# GS_02_Pow.net
KiCad netlist of a schematic drawn in Altium Designer
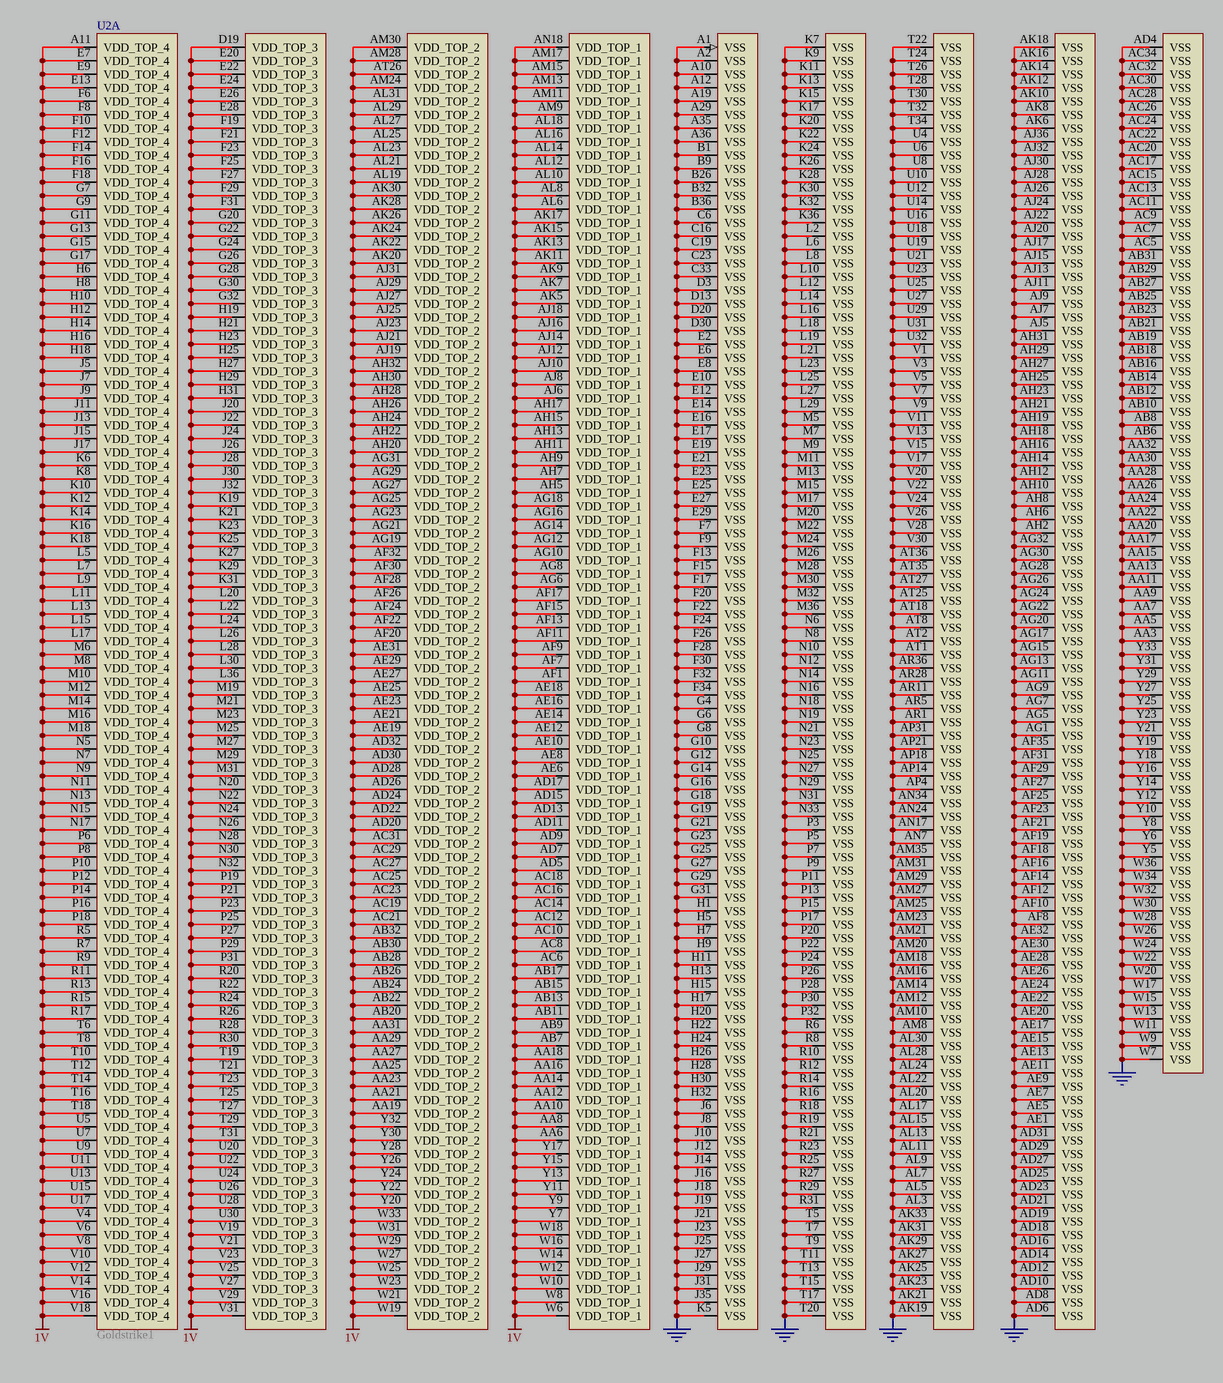
[diagram p0: GS_02_Pow.SchDoc]

(export (version "E")
  (design (tool "Eeschema 10.0.6"))
  (components (comp (ref "U2") (value "Goldstrike1") (libsource (lib "Schlib1") (part "Goldstrike1"))))
  (nets
    (net (code "1") (name "1V") (class "Default")
      (node (ref "U2") (pin "A11") (pinfunction "VDD_TOP_4_A11") (pintype "passive"))
      (node (ref "U2") (pin "AA10") (pinfunction "VDD_TOP_1_AA10") (pintype "passive"))
      (node (ref "U2") (pin "AA12") (pinfunction "VDD_TOP_1_AA12") (pintype "passive"))
      (node (ref "U2") (pin "AA14") (pinfunction "VDD_TOP_1_AA14") (pintype "passive"))
      (node (ref "U2") (pin "AA16") (pinfunction "VDD_TOP_1_AA16") (pintype "passive"))
      (node (ref "U2") (pin "AA18") (pinfunction "VDD_TOP_1_AA18") (pintype "passive"))
      (node (ref "U2") (pin "AA19") (pinfunction "VDD_TOP_2_AA19") (pintype "passive"))
      (node (ref "U2") (pin "AA21") (pinfunction "VDD_TOP_2_AA21") (pintype "passive"))
      (node (ref "U2") (pin "AA23") (pinfunction "VDD_TOP_2_AA23") (pintype "passive"))
      (node (ref "U2") (pin "AA25") (pinfunction "VDD_TOP_2_AA25") (pintype "passive"))
      (node (ref "U2") (pin "AA27") (pinfunction "VDD_TOP_2_AA27") (pintype "passive"))
      (node (ref "U2") (pin "AA29") (pinfunction "VDD_TOP_2_AA29") (pintype "passive"))
      (node (ref "U2") (pin "AA31") (pinfunction "VDD_TOP_2_AA31") (pintype "passive"))
      (node (ref "U2") (pin "AA6") (pinfunction "VDD_TOP_1_AA6") (pintype "passive"))
      (node (ref "U2") (pin "AA8") (pinfunction "VDD_TOP_1_AA8") (pintype "passive"))
      (node (ref "U2") (pin "AB11") (pinfunction "VDD_TOP_1_AB11") (pintype "passive"))
      (node (ref "U2") (pin "AB13") (pinfunction "VDD_TOP_1_AB13") (pintype "passive"))
      (node (ref "U2") (pin "AB15") (pinfunction "VDD_TOP_1_AB15") (pintype "passive"))
      (node (ref "U2") (pin "AB17") (pinfunction "VDD_TOP_1_AB17") (pintype "passive"))
      (node (ref "U2") (pin "AB20") (pinfunction "VDD_TOP_2_AB20") (pintype "passive"))
      (node (ref "U2") (pin "AB22") (pinfunction "VDD_TOP_2_AB22") (pintype "passive"))
      (node (ref "U2") (pin "AB24") (pinfunction "VDD_TOP_2_AB24") (pintype "passive"))
      (node (ref "U2") (pin "AB26") (pinfunction "VDD_TOP_2_AB26") (pintype "passive"))
      (node (ref "U2") (pin "AB28") (pinfunction "VDD_TOP_2_AB28") (pintype "passive"))
      (node (ref "U2") (pin "AB30") (pinfunction "VDD_TOP_2_AB30") (pintype "passive"))
      (node (ref "U2") (pin "AB32") (pinfunction "VDD_TOP_2_AB32") (pintype "passive"))
      (node (ref "U2") (pin "AB7") (pinfunction "VDD_TOP_1_AB7") (pintype "passive"))
      (node (ref "U2") (pin "AB9") (pinfunction "VDD_TOP_1_AB9") (pintype "passive"))
      (node (ref "U2") (pin "AC10") (pinfunction "VDD_TOP_1_AC10") (pintype "passive"))
      (node (ref "U2") (pin "AC12") (pinfunction "VDD_TOP_1_AC12") (pintype "passive"))
      (node (ref "U2") (pin "AC14") (pinfunction "VDD_TOP_1_AC14") (pintype "passive"))
      (node (ref "U2") (pin "AC16") (pinfunction "VDD_TOP_1_AC16") (pintype "passive"))
      (node (ref "U2") (pin "AC18") (pinfunction "VDD_TOP_1_AC18") (pintype "passive"))
      (node (ref "U2") (pin "AC19") (pinfunction "VDD_TOP_2_AC19") (pintype "passive"))
      (node (ref "U2") (pin "AC21") (pinfunction "VDD_TOP_2_AC21") (pintype "passive"))
      (node (ref "U2") (pin "AC23") (pinfunction "VDD_TOP_2_AC23") (pintype "passive"))
      (node (ref "U2") (pin "AC25") (pinfunction "VDD_TOP_2_AC25") (pintype "passive"))
      (node (ref "U2") (pin "AC27") (pinfunction "VDD_TOP_2_AC27") (pintype "passive"))
      (node (ref "U2") (pin "AC29") (pinfunction "VDD_TOP_2_AC29") (pintype "passive"))
      (node (ref "U2") (pin "AC31") (pinfunction "VDD_TOP_2_AC31") (pintype "passive"))
      (node (ref "U2") (pin "AC6") (pinfunction "VDD_TOP_1_AC6") (pintype "passive"))
      (node (ref "U2") (pin "AC8") (pinfunction "VDD_TOP_1_AC8") (pintype "passive"))
      (node (ref "U2") (pin "AD11") (pinfunction "VDD_TOP_1_AD11") (pintype "passive"))
      (node (ref "U2") (pin "AD13") (pinfunction "VDD_TOP_1_AD13") (pintype "passive"))
      (node (ref "U2") (pin "AD15") (pinfunction "VDD_TOP_1_AD15") (pintype "passive"))
      (node (ref "U2") (pin "AD17") (pinfunction "VDD_TOP_1_AD17") (pintype "passive"))
      (node (ref "U2") (pin "AD20") (pinfunction "VDD_TOP_2_AD20") (pintype "passive"))
      (node (ref "U2") (pin "AD22") (pinfunction "VDD_TOP_2_AD22") (pintype "passive"))
      (node (ref "U2") (pin "AD24") (pinfunction "VDD_TOP_2_AD24") (pintype "passive"))
      (node (ref "U2") (pin "AD26") (pinfunction "VDD_TOP_2_AD26") (pintype "passive"))
      (node (ref "U2") (pin "AD28") (pinfunction "VDD_TOP_2_AD28") (pintype "passive"))
      (node (ref "U2") (pin "AD30") (pinfunction "VDD_TOP_2_AD30") (pintype "passive"))
      (node (ref "U2") (pin "AD32") (pinfunction "VDD_TOP_2_AD32") (pintype "passive"))
      (node (ref "U2") (pin "AD5") (pinfunction "VDD_TOP_1_AD5") (pintype "passive"))
      (node (ref "U2") (pin "AD7") (pinfunction "VDD_TOP_1_AD7") (pintype "passive"))
      (node (ref "U2") (pin "AD9") (pinfunction "VDD_TOP_1_AD9") (pintype "passive"))
      (node (ref "U2") (pin "AE10") (pinfunction "VDD_TOP_1_AE10") (pintype "passive"))
      (node (ref "U2") (pin "AE12") (pinfunction "VDD_TOP_1_AE12") (pintype "passive"))
      (node (ref "U2") (pin "AE14") (pinfunction "VDD_TOP_1_AE14") (pintype "passive"))
      (node (ref "U2") (pin "AE16") (pinfunction "VDD_TOP_1_AE16") (pintype "passive"))
      (node (ref "U2") (pin "AE18") (pinfunction "VDD_TOP_1_AE18") (pintype "passive"))
      (node (ref "U2") (pin "AE19") (pinfunction "VDD_TOP_2_AE19") (pintype "passive"))
      (node (ref "U2") (pin "AE21") (pinfunction "VDD_TOP_2_AE21") (pintype "passive"))
      (node (ref "U2") (pin "AE23") (pinfunction "VDD_TOP_2_AE23") (pintype "passive"))
      (node (ref "U2") (pin "AE25") (pinfunction "VDD_TOP_2_AE25") (pintype "passive"))
      (node (ref "U2") (pin "AE27") (pinfunction "VDD_TOP_2_AE27") (pintype "passive"))
      (node (ref "U2") (pin "AE29") (pinfunction "VDD_TOP_2_AE29") (pintype "passive"))
      (node (ref "U2") (pin "AE31") (pinfunction "VDD_TOP_2_AE31") (pintype "passive"))
      (node (ref "U2") (pin "AE6") (pinfunction "VDD_TOP_1_AE6") (pintype "passive"))
      (node (ref "U2") (pin "AE8") (pinfunction "VDD_TOP_1_AE8") (pintype "passive"))
      (node (ref "U2") (pin "AF1") (pinfunction "VDD_TOP_1_AF1") (pintype "passive"))
      (node (ref "U2") (pin "AF11") (pinfunction "VDD_TOP_1_AF11") (pintype "passive"))
      (node (ref "U2") (pin "AF13") (pinfunction "VDD_TOP_1_AF13") (pintype "passive"))
      (node (ref "U2") (pin "AF15") (pinfunction "VDD_TOP_1_AF15") (pintype "passive"))
      (node (ref "U2") (pin "AF17") (pinfunction "VDD_TOP_1_AF17") (pintype "passive"))
      (node (ref "U2") (pin "AF20") (pinfunction "VDD_TOP_2_AF20") (pintype "passive"))
      (node (ref "U2") (pin "AF22") (pinfunction "VDD_TOP_2_AF22") (pintype "passive"))
      (node (ref "U2") (pin "AF24") (pinfunction "VDD_TOP_2_AF24") (pintype "passive"))
      (node (ref "U2") (pin "AF26") (pinfunction "VDD_TOP_2_AF26") (pintype "passive"))
      (node (ref "U2") (pin "AF28") (pinfunction "VDD_TOP_2_AF28") (pintype "passive"))
      (node (ref "U2") (pin "AF30") (pinfunction "VDD_TOP_2_AF30") (pintype "passive"))
      (node (ref "U2") (pin "AF32") (pinfunction "VDD_TOP_2_AF32") (pintype "passive"))
      (node (ref "U2") (pin "AF7") (pinfunction "VDD_TOP_1_AF7") (pintype "passive"))
      (node (ref "U2") (pin "AF9") (pinfunction "VDD_TOP_1_AF9") (pintype "passive"))
      (node (ref "U2") (pin "AG10") (pinfunction "VDD_TOP_1_AG10") (pintype "passive"))
      (node (ref "U2") (pin "AG12") (pinfunction "VDD_TOP_1_AG12") (pintype "passive"))
      (node (ref "U2") (pin "AG14") (pinfunction "VDD_TOP_1_AG14") (pintype "passive"))
      (node (ref "U2") (pin "AG16") (pinfunction "VDD_TOP_1_AG16") (pintype "passive"))
      (node (ref "U2") (pin "AG18") (pinfunction "VDD_TOP_1_AG18") (pintype "passive"))
      (node (ref "U2") (pin "AG19") (pinfunction "VDD_TOP_2_AG19") (pintype "passive"))
      (node (ref "U2") (pin "AG21") (pinfunction "VDD_TOP_2_AG21") (pintype "passive"))
      (node (ref "U2") (pin "AG23") (pinfunction "VDD_TOP_2_AG23") (pintype "passive"))
      (node (ref "U2") (pin "AG25") (pinfunction "VDD_TOP_2_AG25") (pintype "passive"))
      (node (ref "U2") (pin "AG27") (pinfunction "VDD_TOP_2_AG27") (pintype "passive"))
      (node (ref "U2") (pin "AG29") (pinfunction "VDD_TOP_2_AG29") (pintype "passive"))
      (node (ref "U2") (pin "AG31") (pinfunction "VDD_TOP_2_AG31") (pintype "passive"))
      (node (ref "U2") (pin "AG6") (pinfunction "VDD_TOP_1_AG6") (pintype "passive"))
      (node (ref "U2") (pin "AG8") (pinfunction "VDD_TOP_1_AG8") (pintype "passive"))
      (node (ref "U2") (pin "AH11") (pinfunction "VDD_TOP_1_AH11") (pintype "passive"))
      (node (ref "U2") (pin "AH13") (pinfunction "VDD_TOP_1_AH13") (pintype "passive"))
      (node (ref "U2") (pin "AH15") (pinfunction "VDD_TOP_1_AH15") (pintype "passive"))
      (node (ref "U2") (pin "AH17") (pinfunction "VDD_TOP_1_AH17") (pintype "passive"))
      (node (ref "U2") (pin "AH20") (pinfunction "VDD_TOP_2_AH20") (pintype "passive"))
      (node (ref "U2") (pin "AH22") (pinfunction "VDD_TOP_2_AH22") (pintype "passive"))
      (node (ref "U2") (pin "AH24") (pinfunction "VDD_TOP_2_AH24") (pintype "passive"))
      (node (ref "U2") (pin "AH26") (pinfunction "VDD_TOP_2_AH26") (pintype "passive"))
      (node (ref "U2") (pin "AH28") (pinfunction "VDD_TOP_2_AH28") (pintype "passive"))
      (node (ref "U2") (pin "AH30") (pinfunction "VDD_TOP_2_AH30") (pintype "passive"))
      (node (ref "U2") (pin "AH32") (pinfunction "VDD_TOP_2_AH32") (pintype "passive"))
      (node (ref "U2") (pin "AH5") (pinfunction "VDD_TOP_1_AH5") (pintype "passive"))
      (node (ref "U2") (pin "AH7") (pinfunction "VDD_TOP_1_AH7") (pintype "passive"))
      (node (ref "U2") (pin "AH9") (pinfunction "VDD_TOP_1_AH9") (pintype "passive"))
      (node (ref "U2") (pin "AJ10") (pinfunction "VDD_TOP_1_AJ10") (pintype "passive"))
      (node (ref "U2") (pin "AJ12") (pinfunction "VDD_TOP_1_AJ12") (pintype "passive"))
      (node (ref "U2") (pin "AJ14") (pinfunction "VDD_TOP_1_AJ14") (pintype "passive"))
      (node (ref "U2") (pin "AJ16") (pinfunction "VDD_TOP_1_AJ16") (pintype "passive"))
      (node (ref "U2") (pin "AJ18") (pinfunction "VDD_TOP_1_AJ18") (pintype "passive"))
      (node (ref "U2") (pin "AJ19") (pinfunction "VDD_TOP_2_AJ19") (pintype "passive"))
      (node (ref "U2") (pin "AJ21") (pinfunction "VDD_TOP_2_AJ21") (pintype "passive"))
      (node (ref "U2") (pin "AJ23") (pinfunction "VDD_TOP_2_AJ23") (pintype "passive"))
      (node (ref "U2") (pin "AJ25") (pinfunction "VDD_TOP_2_AJ25") (pintype "passive"))
      (node (ref "U2") (pin "AJ27") (pinfunction "VDD_TOP_2_AJ27") (pintype "passive"))
      (node (ref "U2") (pin "AJ29") (pinfunction "VDD_TOP_2_AJ29") (pintype "passive"))
      (node (ref "U2") (pin "AJ31") (pinfunction "VDD_TOP_2_AJ31") (pintype "passive"))
      (node (ref "U2") (pin "AJ6") (pinfunction "VDD_TOP_1_AJ6") (pintype "passive"))
      (node (ref "U2") (pin "AJ8") (pinfunction "VDD_TOP_1_AJ8") (pintype "passive"))
      (node (ref "U2") (pin "AK11") (pinfunction "VDD_TOP_1_AK11") (pintype "passive"))
      (node (ref "U2") (pin "AK13") (pinfunction "VDD_TOP_1_AK13") (pintype "passive"))
      (node (ref "U2") (pin "AK15") (pinfunction "VDD_TOP_1_AK15") (pintype "passive"))
      (node (ref "U2") (pin "AK17") (pinfunction "VDD_TOP_1_AK17") (pintype "passive"))
      (node (ref "U2") (pin "AK20") (pinfunction "VDD_TOP_2_AK20") (pintype "passive"))
      (node (ref "U2") (pin "AK22") (pinfunction "VDD_TOP_2_AK22") (pintype "passive"))
      (node (ref "U2") (pin "AK24") (pinfunction "VDD_TOP_2_AK24") (pintype "passive"))
      (node (ref "U2") (pin "AK26") (pinfunction "VDD_TOP_2_AK26") (pintype "passive"))
      (node (ref "U2") (pin "AK28") (pinfunction "VDD_TOP_2_AK28") (pintype "passive"))
      (node (ref "U2") (pin "AK30") (pinfunction "VDD_TOP_2_AK30") (pintype "passive"))
      (node (ref "U2") (pin "AK5") (pinfunction "VDD_TOP_1_AK5") (pintype "passive"))
      (node (ref "U2") (pin "AK7") (pinfunction "VDD_TOP_1_AK7") (pintype "passive"))
      (node (ref "U2") (pin "AK9") (pinfunction "VDD_TOP_1_AK9") (pintype "passive"))
      (node (ref "U2") (pin "AL10") (pinfunction "VDD_TOP_1_AL10") (pintype "passive"))
      (node (ref "U2") (pin "AL12") (pinfunction "VDD_TOP_1_AL12") (pintype "passive"))
      (node (ref "U2") (pin "AL14") (pinfunction "VDD_TOP_1_AL14") (pintype "passive"))
      (node (ref "U2") (pin "AL16") (pinfunction "VDD_TOP_1_AL16") (pintype "passive"))
      (node (ref "U2") (pin "AL18") (pinfunction "VDD_TOP_1_AL18") (pintype "passive"))
      (node (ref "U2") (pin "AL19") (pinfunction "VDD_TOP_2_AL19") (pintype "passive"))
      (node (ref "U2") (pin "AL21") (pinfunction "VDD_TOP_2_AL21") (pintype "passive"))
      (node (ref "U2") (pin "AL23") (pinfunction "VDD_TOP_2_AL23") (pintype "passive"))
      (node (ref "U2") (pin "AL25") (pinfunction "VDD_TOP_2_AL25") (pintype "passive"))
      (node (ref "U2") (pin "AL27") (pinfunction "VDD_TOP_2_AL27") (pintype "passive"))
      (node (ref "U2") (pin "AL29") (pinfunction "VDD_TOP_2_AL29") (pintype "passive"))
      (node (ref "U2") (pin "AL31") (pinfunction "VDD_TOP_2_AL31") (pintype "passive"))
      (node (ref "U2") (pin "AL6") (pinfunction "VDD_TOP_1_AL6") (pintype "passive"))
      (node (ref "U2") (pin "AL8") (pinfunction "VDD_TOP_1_AL8") (pintype "passive"))
      (node (ref "U2") (pin "AM11") (pinfunction "VDD_TOP_1_AM11") (pintype "passive"))
      (node (ref "U2") (pin "AM13") (pinfunction "VDD_TOP_1_AM13") (pintype "passive"))
      (node (ref "U2") (pin "AM15") (pinfunction "VDD_TOP_1_AM15") (pintype "passive"))
      (node (ref "U2") (pin "AM17") (pinfunction "VDD_TOP_1_AM17") (pintype "passive"))
      (node (ref "U2") (pin "AM24") (pinfunction "VDD_TOP_2_AM24") (pintype "passive"))
      (node (ref "U2") (pin "AM28") (pinfunction "VDD_TOP_2_AM28") (pintype "passive"))
      (node (ref "U2") (pin "AM30") (pinfunction "VDD_TOP_2_AM30") (pintype "passive"))
      (node (ref "U2") (pin "AM9") (pinfunction "VDD_TOP_1_AM9") (pintype "passive"))
      (node (ref "U2") (pin "AN18") (pinfunction "VDD_TOP_1_AN18") (pintype "passive"))
      (node (ref "U2") (pin "AT26") (pinfunction "VDD_TOP_2_AT26") (pintype "passive"))
      (node (ref "U2") (pin "D19") (pinfunction "VDD_TOP_3_D19") (pintype "passive"))
      (node (ref "U2") (pin "E13") (pinfunction "VDD_TOP_4_E13") (pintype "passive"))
      (node (ref "U2") (pin "E20") (pinfunction "VDD_TOP_3_E20") (pintype "passive"))
      (node (ref "U2") (pin "E22") (pinfunction "VDD_TOP_3_E22") (pintype "passive"))
      (node (ref "U2") (pin "E24") (pinfunction "VDD_TOP_3_E24") (pintype "passive"))
      (node (ref "U2") (pin "E26") (pinfunction "VDD_TOP_3_E26") (pintype "passive"))
      (node (ref "U2") (pin "E28") (pinfunction "VDD_TOP_3_E28") (pintype "passive"))
      (node (ref "U2") (pin "E7") (pinfunction "VDD_TOP_4_E7") (pintype "passive"))
      (node (ref "U2") (pin "E9") (pinfunction "VDD_TOP_4_E9") (pintype "passive"))
      (node (ref "U2") (pin "F10") (pinfunction "VDD_TOP_4_F10") (pintype "passive"))
      (node (ref "U2") (pin "F12") (pinfunction "VDD_TOP_4_F12") (pintype "passive"))
      (node (ref "U2") (pin "F14") (pinfunction "VDD_TOP_4_F14") (pintype "passive"))
      (node (ref "U2") (pin "F16") (pinfunction "VDD_TOP_4_F16") (pintype "passive"))
      (node (ref "U2") (pin "F18") (pinfunction "VDD_TOP_4_F18") (pintype "passive"))
      (node (ref "U2") (pin "F19") (pinfunction "VDD_TOP_3_F19") (pintype "passive"))
      (node (ref "U2") (pin "F21") (pinfunction "VDD_TOP_3_F21") (pintype "passive"))
      (node (ref "U2") (pin "F23") (pinfunction "VDD_TOP_3_F23") (pintype "passive"))
      (node (ref "U2") (pin "F25") (pinfunction "VDD_TOP_3_F25") (pintype "passive"))
      (node (ref "U2") (pin "F27") (pinfunction "VDD_TOP_3_F27") (pintype "passive"))
      (node (ref "U2") (pin "F29") (pinfunction "VDD_TOP_3_F29") (pintype "passive"))
      (node (ref "U2") (pin "F31") (pinfunction "VDD_TOP_3_F31") (pintype "passive"))
      (node (ref "U2") (pin "F6") (pinfunction "VDD_TOP_4_F6") (pintype "passive"))
      (node (ref "U2") (pin "F8") (pinfunction "VDD_TOP_4_F8") (pintype "passive"))
      (node (ref "U2") (pin "G11") (pinfunction "VDD_TOP_4_G11") (pintype "passive"))
      (node (ref "U2") (pin "G13") (pinfunction "VDD_TOP_4_G13") (pintype "passive"))
      (node (ref "U2") (pin "G15") (pinfunction "VDD_TOP_4_G15") (pintype "passive"))
      (node (ref "U2") (pin "G17") (pinfunction "VDD_TOP_4_G17") (pintype "passive"))
      (node (ref "U2") (pin "G20") (pinfunction "VDD_TOP_3_G20") (pintype "passive"))
      (node (ref "U2") (pin "G22") (pinfunction "VDD_TOP_3_G22") (pintype "passive"))
      (node (ref "U2") (pin "G24") (pinfunction "VDD_TOP_3_G24") (pintype "passive"))
      (node (ref "U2") (pin "G26") (pinfunction "VDD_TOP_3_G26") (pintype "passive"))
      (node (ref "U2") (pin "G28") (pinfunction "VDD_TOP_3_G28") (pintype "passive"))
      (node (ref "U2") (pin "G30") (pinfunction "VDD_TOP_3_G30") (pintype "passive"))
      (node (ref "U2") (pin "G32") (pinfunction "VDD_TOP_3_G32") (pintype "passive"))
      (node (ref "U2") (pin "G7") (pinfunction "VDD_TOP_4_G7") (pintype "passive"))
      (node (ref "U2") (pin "G9") (pinfunction "VDD_TOP_4_G9") (pintype "passive"))
      (node (ref "U2") (pin "H10") (pinfunction "VDD_TOP_4_H10") (pintype "passive"))
      (node (ref "U2") (pin "H12") (pinfunction "VDD_TOP_4_H12") (pintype "passive"))
      (node (ref "U2") (pin "H14") (pinfunction "VDD_TOP_4_H14") (pintype "passive"))
      (node (ref "U2") (pin "H16") (pinfunction "VDD_TOP_4_H16") (pintype "passive"))
      (node (ref "U2") (pin "H18") (pinfunction "VDD_TOP_4_H18") (pintype "passive"))
      (node (ref "U2") (pin "H19") (pinfunction "VDD_TOP_3_H19") (pintype "passive"))
      (node (ref "U2") (pin "H21") (pinfunction "VDD_TOP_3_H21") (pintype "passive"))
      (node (ref "U2") (pin "H23") (pinfunction "VDD_TOP_3_H23") (pintype "passive"))
      (node (ref "U2") (pin "H25") (pinfunction "VDD_TOP_3_H25") (pintype "passive"))
      (node (ref "U2") (pin "H27") (pinfunction "VDD_TOP_3_H27") (pintype "passive"))
      (node (ref "U2") (pin "H29") (pinfunction "VDD_TOP_3_H29") (pintype "passive"))
      (node (ref "U2") (pin "H31") (pinfunction "VDD_TOP_3_H31") (pintype "passive"))
      (node (ref "U2") (pin "H6") (pinfunction "VDD_TOP_4_H6") (pintype "passive"))
      (node (ref "U2") (pin "H8") (pinfunction "VDD_TOP_4_H8") (pintype "passive"))
      (node (ref "U2") (pin "J11") (pinfunction "VDD_TOP_4_J11") (pintype "passive"))
      (node (ref "U2") (pin "J13") (pinfunction "VDD_TOP_4_J13") (pintype "passive"))
      (node (ref "U2") (pin "J15") (pinfunction "VDD_TOP_4_J15") (pintype "passive"))
      (node (ref "U2") (pin "J17") (pinfunction "VDD_TOP_4_J17") (pintype "passive"))
      (node (ref "U2") (pin "J20") (pinfunction "VDD_TOP_3_J20") (pintype "passive"))
      (node (ref "U2") (pin "J22") (pinfunction "VDD_TOP_3_J22") (pintype "passive"))
      (node (ref "U2") (pin "J24") (pinfunction "VDD_TOP_3_J24") (pintype "passive"))
      (node (ref "U2") (pin "J26") (pinfunction "VDD_TOP_3_J26") (pintype "passive"))
      (node (ref "U2") (pin "J28") (pinfunction "VDD_TOP_3_J28") (pintype "passive"))
      (node (ref "U2") (pin "J30") (pinfunction "VDD_TOP_3_J30") (pintype "passive"))
      (node (ref "U2") (pin "J32") (pinfunction "VDD_TOP_3_J32") (pintype "passive"))
      (node (ref "U2") (pin "J5") (pinfunction "VDD_TOP_4_J5") (pintype "passive"))
      (node (ref "U2") (pin "J7") (pinfunction "VDD_TOP_4_J7") (pintype "passive"))
      (node (ref "U2") (pin "J9") (pinfunction "VDD_TOP_4_J9") (pintype "passive"))
      (node (ref "U2") (pin "K10") (pinfunction "VDD_TOP_4_K10") (pintype "passive"))
      (node (ref "U2") (pin "K12") (pinfunction "VDD_TOP_4_K12") (pintype "passive"))
      (node (ref "U2") (pin "K14") (pinfunction "VDD_TOP_4_K14") (pintype "passive"))
      (node (ref "U2") (pin "K16") (pinfunction "VDD_TOP_4_K16") (pintype "passive"))
      (node (ref "U2") (pin "K18") (pinfunction "VDD_TOP_4_K18") (pintype "passive"))
      (node (ref "U2") (pin "K19") (pinfunction "VDD_TOP_3_K19") (pintype "passive"))
      (node (ref "U2") (pin "K21") (pinfunction "VDD_TOP_3_K21") (pintype "passive"))
      (node (ref "U2") (pin "K23") (pinfunction "VDD_TOP_3_K23") (pintype "passive"))
      (node (ref "U2") (pin "K25") (pinfunction "VDD_TOP_3_K25") (pintype "passive"))
      (node (ref "U2") (pin "K27") (pinfunction "VDD_TOP_3_K27") (pintype "passive"))
      (node (ref "U2") (pin "K29") (pinfunction "VDD_TOP_3_K29") (pintype "passive"))
      (node (ref "U2") (pin "K31") (pinfunction "VDD_TOP_3_K31") (pintype "passive"))
      (node (ref "U2") (pin "K6") (pinfunction "VDD_TOP_4_K6") (pintype "passive"))
      (node (ref "U2") (pin "K8") (pinfunction "VDD_TOP_4_K8") (pintype "passive"))
      (node (ref "U2") (pin "L11") (pinfunction "VDD_TOP_4_L11") (pintype "passive"))
      (node (ref "U2") (pin "L13") (pinfunction "VDD_TOP_4_L13") (pintype "passive"))
      (node (ref "U2") (pin "L15") (pinfunction "VDD_TOP_4_L15") (pintype "passive"))
      (node (ref "U2") (pin "L17") (pinfunction "VDD_TOP_4_L17") (pintype "passive"))
      (node (ref "U2") (pin "L20") (pinfunction "VDD_TOP_3_L20") (pintype "passive"))
      (node (ref "U2") (pin "L22") (pinfunction "VDD_TOP_3_L22") (pintype "passive"))
      (node (ref "U2") (pin "L24") (pinfunction "VDD_TOP_3_L24") (pintype "passive"))
      (node (ref "U2") (pin "L26") (pinfunction "VDD_TOP_3_L26") (pintype "passive"))
      (node (ref "U2") (pin "L28") (pinfunction "VDD_TOP_3_L28") (pintype "passive"))
      (node (ref "U2") (pin "L30") (pinfunction "VDD_TOP_3_L30") (pintype "passive"))
      (node (ref "U2") (pin "L36") (pinfunction "VDD_TOP_3_L36") (pintype "passive"))
      (node (ref "U2") (pin "L5") (pinfunction "VDD_TOP_4_L5") (pintype "passive"))
      (node (ref "U2") (pin "L7") (pinfunction "VDD_TOP_4_L7") (pintype "passive"))
      (node (ref "U2") (pin "L9") (pinfunction "VDD_TOP_4_L9") (pintype "passive"))
      (node (ref "U2") (pin "M10") (pinfunction "VDD_TOP_4_M10") (pintype "passive"))
      (node (ref "U2") (pin "M12") (pinfunction "VDD_TOP_4_M12") (pintype "passive"))
      (node (ref "U2") (pin "M14") (pinfunction "VDD_TOP_4_M14") (pintype "passive"))
      (node (ref "U2") (pin "M16") (pinfunction "VDD_TOP_4_M16") (pintype "passive"))
      (node (ref "U2") (pin "M18") (pinfunction "VDD_TOP_4_M18") (pintype "passive"))
      (node (ref "U2") (pin "M19") (pinfunction "VDD_TOP_3_M19") (pintype "passive"))
      (node (ref "U2") (pin "M21") (pinfunction "VDD_TOP_3_M21") (pintype "passive"))
      (node (ref "U2") (pin "M23") (pinfunction "VDD_TOP_3_M23") (pintype "passive"))
      (node (ref "U2") (pin "M25") (pinfunction "VDD_TOP_3_M25") (pintype "passive"))
      (node (ref "U2") (pin "M27") (pinfunction "VDD_TOP_3_M27") (pintype "passive"))
      (node (ref "U2") (pin "M29") (pinfunction "VDD_TOP_3_M29") (pintype "passive"))
      (node (ref "U2") (pin "M31") (pinfunction "VDD_TOP_3_M31") (pintype "passive"))
      (node (ref "U2") (pin "M6") (pinfunction "VDD_TOP_4_M6") (pintype "passive"))
      (node (ref "U2") (pin "M8") (pinfunction "VDD_TOP_4_M8") (pintype "passive"))
      (node (ref "U2") (pin "N11") (pinfunction "VDD_TOP_4_N11") (pintype "passive"))
      (node (ref "U2") (pin "N13") (pinfunction "VDD_TOP_4_N13") (pintype "passive"))
      (node (ref "U2") (pin "N15") (pinfunction "VDD_TOP_4_N15") (pintype "passive"))
      (node (ref "U2") (pin "N17") (pinfunction "VDD_TOP_4_N17") (pintype "passive"))
      (node (ref "U2") (pin "N20") (pinfunction "VDD_TOP_3_N20") (pintype "passive"))
      (node (ref "U2") (pin "N22") (pinfunction "VDD_TOP_3_N22") (pintype "passive"))
      (node (ref "U2") (pin "N24") (pinfunction "VDD_TOP_3_N24") (pintype "passive"))
      (node (ref "U2") (pin "N26") (pinfunction "VDD_TOP_3_N26") (pintype "passive"))
      (node (ref "U2") (pin "N28") (pinfunction "VDD_TOP_3_N28") (pintype "passive"))
      (node (ref "U2") (pin "N30") (pinfunction "VDD_TOP_3_N30") (pintype "passive"))
      (node (ref "U2") (pin "N32") (pinfunction "VDD_TOP_3_N32") (pintype "passive"))
      (node (ref "U2") (pin "N5") (pinfunction "VDD_TOP_4_N5") (pintype "passive"))
      (node (ref "U2") (pin "N7") (pinfunction "VDD_TOP_4_N7") (pintype "passive"))
      (node (ref "U2") (pin "N9") (pinfunction "VDD_TOP_4_N9") (pintype "passive"))
      (node (ref "U2") (pin "P10") (pinfunction "VDD_TOP_4_P10") (pintype "passive"))
      (node (ref "U2") (pin "P12") (pinfunction "VDD_TOP_4_P12") (pintype "passive"))
      (node (ref "U2") (pin "P14") (pinfunction "VDD_TOP_4_P14") (pintype "passive"))
      (node (ref "U2") (pin "P16") (pinfunction "VDD_TOP_4_P16") (pintype "passive"))
      (node (ref "U2") (pin "P18") (pinfunction "VDD_TOP_4_P18") (pintype "passive"))
      (node (ref "U2") (pin "P19") (pinfunction "VDD_TOP_3_P19") (pintype "passive"))
      (node (ref "U2") (pin "P21") (pinfunction "VDD_TOP_3_P21") (pintype "passive"))
      (node (ref "U2") (pin "P23") (pinfunction "VDD_TOP_3_P23") (pintype "passive"))
      (node (ref "U2") (pin "P25") (pinfunction "VDD_TOP_3_P25") (pintype "passive"))
      (node (ref "U2") (pin "P27") (pinfunction "VDD_TOP_3_P27") (pintype "passive"))
      (node (ref "U2") (pin "P29") (pinfunction "VDD_TOP_3_P29") (pintype "passive"))
      (node (ref "U2") (pin "P31") (pinfunction "VDD_TOP_3_P31") (pintype "passive"))
      (node (ref "U2") (pin "P6") (pinfunction "VDD_TOP_4_P6") (pintype "passive"))
      (node (ref "U2") (pin "P8") (pinfunction "VDD_TOP_4_P8") (pintype "passive"))
      (node (ref "U2") (pin "R11") (pinfunction "VDD_TOP_4_R11") (pintype "passive"))
      (node (ref "U2") (pin "R13") (pinfunction "VDD_TOP_4_R13") (pintype "passive"))
      (node (ref "U2") (pin "R15") (pinfunction "VDD_TOP_4_R15") (pintype "passive"))
      (node (ref "U2") (pin "R17") (pinfunction "VDD_TOP_4_R17") (pintype "passive"))
      (node (ref "U2") (pin "R20") (pinfunction "VDD_TOP_3_R20") (pintype "passive"))
      (node (ref "U2") (pin "R22") (pinfunction "VDD_TOP_3_R22") (pintype "passive"))
      (node (ref "U2") (pin "R24") (pinfunction "VDD_TOP_3_R24") (pintype "passive"))
      (node (ref "U2") (pin "R26") (pinfunction "VDD_TOP_3_R26") (pintype "passive"))
      (node (ref "U2") (pin "R28") (pinfunction "VDD_TOP_3_R28") (pintype "passive"))
      (node (ref "U2") (pin "R30") (pinfunction "VDD_TOP_3_R30") (pintype "passive"))
      (node (ref "U2") (pin "R5") (pinfunction "VDD_TOP_4_R5") (pintype "passive"))
      (node (ref "U2") (pin "R7") (pinfunction "VDD_TOP_4_R7") (pintype "passive"))
      (node (ref "U2") (pin "R9") (pinfunction "VDD_TOP_4_R9") (pintype "passive"))
      (node (ref "U2") (pin "T10") (pinfunction "VDD_TOP_4_T10") (pintype "passive"))
      (node (ref "U2") (pin "T12") (pinfunction "VDD_TOP_4_T12") (pintype "passive"))
      (node (ref "U2") (pin "T14") (pinfunction "VDD_TOP_4_T14") (pintype "passive"))
      (node (ref "U2") (pin "T16") (pinfunction "VDD_TOP_4_T16") (pintype "passive"))
      (node (ref "U2") (pin "T18") (pinfunction "VDD_TOP_4_T18") (pintype "passive"))
      (node (ref "U2") (pin "T19") (pinfunction "VDD_TOP_3_T19") (pintype "passive"))
      (node (ref "U2") (pin "T21") (pinfunction "VDD_TOP_3_T21") (pintype "passive"))
      (node (ref "U2") (pin "T23") (pinfunction "VDD_TOP_3_T23") (pintype "passive"))
      (node (ref "U2") (pin "T25") (pinfunction "VDD_TOP_3_T25") (pintype "passive"))
      (node (ref "U2") (pin "T27") (pinfunction "VDD_TOP_3_T27") (pintype "passive"))
      (node (ref "U2") (pin "T29") (pinfunction "VDD_TOP_3_T29") (pintype "passive"))
      (node (ref "U2") (pin "T31") (pinfunction "VDD_TOP_3_T31") (pintype "passive"))
      (node (ref "U2") (pin "T6") (pinfunction "VDD_TOP_4_T6") (pintype "passive"))
      (node (ref "U2") (pin "T8") (pinfunction "VDD_TOP_4_T8") (pintype "passive"))
      (node (ref "U2") (pin "U11") (pinfunction "VDD_TOP_4_U11") (pintype "passive"))
      (node (ref "U2") (pin "U13") (pinfunction "VDD_TOP_4_U13") (pintype "passive"))
      (node (ref "U2") (pin "U15") (pinfunction "VDD_TOP_4_U15") (pintype "passive"))
      (node (ref "U2") (pin "U17") (pinfunction "VDD_TOP_4_U17") (pintype "passive"))
      (node (ref "U2") (pin "U20") (pinfunction "VDD_TOP_3_U20") (pintype "passive"))
      (node (ref "U2") (pin "U22") (pinfunction "VDD_TOP_3_U22") (pintype "passive"))
      (node (ref "U2") (pin "U24") (pinfunction "VDD_TOP_3_U24") (pintype "passive"))
      (node (ref "U2") (pin "U26") (pinfunction "VDD_TOP_3_U26") (pintype "passive"))
      (node (ref "U2") (pin "U28") (pinfunction "VDD_TOP_3_U28") (pintype "passive"))
      (node (ref "U2") (pin "U30") (pinfunction "VDD_TOP_3_U30") (pintype "passive"))
      (node (ref "U2") (pin "U5") (pinfunction "VDD_TOP_4_U5") (pintype "passive"))
      (node (ref "U2") (pin "U7") (pinfunction "VDD_TOP_4_U7") (pintype "passive"))
      (node (ref "U2") (pin "U9") (pinfunction "VDD_TOP_4_U9") (pintype "passive"))
      (node (ref "U2") (pin "V10") (pinfunction "VDD_TOP_4_V10") (pintype "passive"))
      (node (ref "U2") (pin "V12") (pinfunction "VDD_TOP_4_V12") (pintype "passive"))
      (node (ref "U2") (pin "V14") (pinfunction "VDD_TOP_4_V14") (pintype "passive"))
      (node (ref "U2") (pin "V16") (pinfunction "VDD_TOP_4_V16") (pintype "passive"))
      (node (ref "U2") (pin "V18") (pinfunction "VDD_TOP_4_V18") (pintype "passive"))
      (node (ref "U2") (pin "V19") (pinfunction "VDD_TOP_3_V19") (pintype "passive"))
      (node (ref "U2") (pin "V21") (pinfunction "VDD_TOP_3_V21") (pintype "passive"))
      (node (ref "U2") (pin "V23") (pinfunction "VDD_TOP_3_V23") (pintype "passive"))
      (node (ref "U2") (pin "V25") (pinfunction "VDD_TOP_3_V25") (pintype "passive"))
      (node (ref "U2") (pin "V27") (pinfunction "VDD_TOP_3_V27") (pintype "passive"))
      (node (ref "U2") (pin "V29") (pinfunction "VDD_TOP_3_V29") (pintype "passive"))
      (node (ref "U2") (pin "V31") (pinfunction "VDD_TOP_3_V31") (pintype "passive"))
      (node (ref "U2") (pin "V4") (pinfunction "VDD_TOP_4_V4") (pintype "passive"))
      (node (ref "U2") (pin "V6") (pinfunction "VDD_TOP_4_V6") (pintype "passive"))
      (node (ref "U2") (pin "V8") (pinfunction "VDD_TOP_4_V8") (pintype "passive"))
      (node (ref "U2") (pin "W10") (pinfunction "VDD_TOP_1_W10") (pintype "passive"))
      (node (ref "U2") (pin "W12") (pinfunction "VDD_TOP_1_W12") (pintype "passive"))
      (node (ref "U2") (pin "W14") (pinfunction "VDD_TOP_1_W14") (pintype "passive"))
      (node (ref "U2") (pin "W16") (pinfunction "VDD_TOP_1_W16") (pintype "passive"))
      (node (ref "U2") (pin "W18") (pinfunction "VDD_TOP_1_W18") (pintype "passive"))
      (node (ref "U2") (pin "W19") (pinfunction "VDD_TOP_2_W19") (pintype "passive"))
      (node (ref "U2") (pin "W21") (pinfunction "VDD_TOP_2_W21") (pintype "passive"))
      (node (ref "U2") (pin "W23") (pinfunction "VDD_TOP_2_W23") (pintype "passive"))
      (node (ref "U2") (pin "W25") (pinfunction "VDD_TOP_2_W25") (pintype "passive"))
      (node (ref "U2") (pin "W27") (pinfunction "VDD_TOP_2_W27") (pintype "passive"))
      (node (ref "U2") (pin "W29") (pinfunction "VDD_TOP_2_W29") (pintype "passive"))
      (node (ref "U2") (pin "W31") (pinfunction "VDD_TOP_2_W31") (pintype "passive"))
      (node (ref "U2") (pin "W33") (pinfunction "VDD_TOP_2_W33") (pintype "passive"))
      (node (ref "U2") (pin "W6") (pinfunction "VDD_TOP_1_W6") (pintype "passive"))
      (node (ref "U2") (pin "W8") (pinfunction "VDD_TOP_1_W8") (pintype "passive"))
      (node (ref "U2") (pin "Y11") (pinfunction "VDD_TOP_1_Y11") (pintype "passive"))
      (node (ref "U2") (pin "Y13") (pinfunction "VDD_TOP_1_Y13") (pintype "passive"))
      (node (ref "U2") (pin "Y15") (pinfunction "VDD_TOP_1_Y15") (pintype "passive"))
      (node (ref "U2") (pin "Y17") (pinfunction "VDD_TOP_1_Y17") (pintype "passive"))
      (node (ref "U2") (pin "Y20") (pinfunction "VDD_TOP_2_Y20") (pintype "passive"))
      (node (ref "U2") (pin "Y22") (pinfunction "VDD_TOP_2_Y22") (pintype "passive"))
      (node (ref "U2") (pin "Y24") (pinfunction "VDD_TOP_2_Y24") (pintype "passive"))
      (node (ref "U2") (pin "Y26") (pinfunction "VDD_TOP_2_Y26") (pintype "passive"))
      (node (ref "U2") (pin "Y28") (pinfunction "VDD_TOP_2_Y28") (pintype "passive"))
      (node (ref "U2") (pin "Y30") (pinfunction "VDD_TOP_2_Y30") (pintype "passive"))
      (node (ref "U2") (pin "Y32") (pinfunction "VDD_TOP_2_Y32") (pintype "passive"))
      (node (ref "U2") (pin "Y7") (pinfunction "VDD_TOP_1_Y7") (pintype "passive"))
      (node (ref "U2") (pin "Y9") (pinfunction "VDD_TOP_1_Y9") (pintype "passive"))
    )
    (net (code "2") (name "GND") (class "Default")
      (node (ref "U2") (pin "A1") (pinfunction "VSS_A1") (pintype "input"))
      (node (ref "U2") (pin "A10") (pinfunction "VSS_A10") (pintype "passive"))
      (node (ref "U2") (pin "A12") (pinfunction "VSS_A12") (pintype "passive"))
      (node (ref "U2") (pin "A19") (pinfunction "VSS_A19") (pintype "passive"))
      (node (ref "U2") (pin "A2") (pinfunction "VSS_A2") (pintype "passive"))
      (node (ref "U2") (pin "A29") (pinfunction "VSS_A29") (pintype "passive"))
      (node (ref "U2") (pin "A35") (pinfunction "VSS_A35") (pintype "passive"))
      (node (ref "U2") (pin "A36") (pinfunction "VSS_A36") (pintype "passive"))
      (node (ref "U2") (pin "AA11") (pinfunction "VSS_AA11") (pintype "passive"))
      (node (ref "U2") (pin "AA13") (pinfunction "VSS_AA13") (pintype "passive"))
      (node (ref "U2") (pin "AA15") (pinfunction "VSS_AA15") (pintype "passive"))
      (node (ref "U2") (pin "AA17") (pinfunction "VSS_AA17") (pintype "passive"))
      (node (ref "U2") (pin "AA20") (pinfunction "VSS_AA20") (pintype "passive"))
      (node (ref "U2") (pin "AA22") (pinfunction "VSS_AA22") (pintype "passive"))
      (node (ref "U2") (pin "AA24") (pinfunction "VSS_AA24") (pintype "passive"))
      (node (ref "U2") (pin "AA26") (pinfunction "VSS_AA26") (pintype "passive"))
      (node (ref "U2") (pin "AA28") (pinfunction "VSS_AA28") (pintype "passive"))
      (node (ref "U2") (pin "AA3") (pinfunction "VSS_AA3") (pintype "passive"))
      (node (ref "U2") (pin "AA30") (pinfunction "VSS_AA30") (pintype "passive"))
      (node (ref "U2") (pin "AA32") (pinfunction "VSS_AA32") (pintype "passive"))
      (node (ref "U2") (pin "AA5") (pinfunction "VSS_AA5") (pintype "passive"))
      (node (ref "U2") (pin "AA7") (pinfunction "VSS_AA7") (pintype "passive"))
      (node (ref "U2") (pin "AA9") (pinfunction "VSS_AA9") (pintype "passive"))
      (node (ref "U2") (pin "AB10") (pinfunction "VSS_AB10") (pintype "passive"))
      (node (ref "U2") (pin "AB12") (pinfunction "VSS_AB12") (pintype "passive"))
      (node (ref "U2") (pin "AB14") (pinfunction "VSS_AB14") (pintype "passive"))
      (node (ref "U2") (pin "AB16") (pinfunction "VSS_AB16") (pintype "passive"))
      (node (ref "U2") (pin "AB18") (pinfunction "VSS_AB18") (pintype "passive"))
      (node (ref "U2") (pin "AB19") (pinfunction "VSS_AB19") (pintype "passive"))
      (node (ref "U2") (pin "AB21") (pinfunction "VSS_AB21") (pintype "passive"))
      (node (ref "U2") (pin "AB23") (pinfunction "VSS_AB23") (pintype "passive"))
      (node (ref "U2") (pin "AB25") (pinfunction "VSS_AB25") (pintype "passive"))
      (node (ref "U2") (pin "AB27") (pinfunction "VSS_AB27") (pintype "passive"))
      (node (ref "U2") (pin "AB29") (pinfunction "VSS_AB29") (pintype "passive"))
      (node (ref "U2") (pin "AB31") (pinfunction "VSS_AB31") (pintype "passive"))
      (node (ref "U2") (pin "AB6") (pinfunction "VSS_AB6") (pintype "passive"))
      (node (ref "U2") (pin "AB8") (pinfunction "VSS_AB8") (pintype "passive"))
      (node (ref "U2") (pin "AC11") (pinfunction "VSS_AC11") (pintype "passive"))
      (node (ref "U2") (pin "AC13") (pinfunction "VSS_AC13") (pintype "passive"))
      (node (ref "U2") (pin "AC15") (pinfunction "VSS_AC15") (pintype "passive"))
      (node (ref "U2") (pin "AC17") (pinfunction "VSS_AC17") (pintype "passive"))
      (node (ref "U2") (pin "AC20") (pinfunction "VSS_AC20") (pintype "passive"))
      (node (ref "U2") (pin "AC22") (pinfunction "VSS_AC22") (pintype "passive"))
      (node (ref "U2") (pin "AC24") (pinfunction "VSS_AC24") (pintype "passive"))
      (node (ref "U2") (pin "AC26") (pinfunction "VSS_AC26") (pintype "passive"))
      (node (ref "U2") (pin "AC28") (pinfunction "VSS_AC28") (pintype "passive"))
      (node (ref "U2") (pin "AC30") (pinfunction "VSS_AC30") (pintype "passive"))
      (node (ref "U2") (pin "AC32") (pinfunction "VSS_AC32") (pintype "passive"))
      (node (ref "U2") (pin "AC34") (pinfunction "VSS_AC34") (pintype "passive"))
      (node (ref "U2") (pin "AC5") (pinfunction "VSS_AC5") (pintype "passive"))
      (node (ref "U2") (pin "AC7") (pinfunction "VSS_AC7") (pintype "passive"))
      (node (ref "U2") (pin "AC9") (pinfunction "VSS_AC9") (pintype "passive"))
      (node (ref "U2") (pin "AD10") (pinfunction "VSS_AD10") (pintype "passive"))
      (node (ref "U2") (pin "AD12") (pinfunction "VSS_AD12") (pintype "passive"))
      (node (ref "U2") (pin "AD14") (pinfunction "VSS_AD14") (pintype "passive"))
      (node (ref "U2") (pin "AD16") (pinfunction "VSS_AD16") (pintype "passive"))
      (node (ref "U2") (pin "AD18") (pinfunction "VSS_AD18") (pintype "passive"))
      (node (ref "U2") (pin "AD19") (pinfunction "VSS_AD19") (pintype "passive"))
      (node (ref "U2") (pin "AD21") (pinfunction "VSS_AD21") (pintype "passive"))
      (node (ref "U2") (pin "AD23") (pinfunction "VSS_AD23") (pintype "passive"))
      (node (ref "U2") (pin "AD25") (pinfunction "VSS_AD25") (pintype "passive"))
      (node (ref "U2") (pin "AD27") (pinfunction "VSS_AD27") (pintype "passive"))
      (node (ref "U2") (pin "AD29") (pinfunction "VSS_AD29") (pintype "passive"))
      (node (ref "U2") (pin "AD31") (pinfunction "VSS_AD31") (pintype "passive"))
      (node (ref "U2") (pin "AD4") (pinfunction "VSS_AD4") (pintype "passive"))
      (node (ref "U2") (pin "AD6") (pinfunction "VSS_AD6") (pintype "passive"))
      (node (ref "U2") (pin "AD8") (pinfunction "VSS_AD8") (pintype "passive"))
      (node (ref "U2") (pin "AE1") (pinfunction "VSS_AE1") (pintype "passive"))
      (node (ref "U2") (pin "AE11") (pinfunction "VSS_AE11") (pintype "passive"))
      (node (ref "U2") (pin "AE13") (pinfunction "VSS_AE13") (pintype "passive"))
      (node (ref "U2") (pin "AE15") (pinfunction "VSS_AE15") (pintype "passive"))
      (node (ref "U2") (pin "AE17") (pinfunction "VSS_AE17") (pintype "passive"))
      (node (ref "U2") (pin "AE20") (pinfunction "VSS_AE20") (pintype "passive"))
      (node (ref "U2") (pin "AE22") (pinfunction "VSS_AE22") (pintype "passive"))
      (node (ref "U2") (pin "AE24") (pinfunction "VSS_AE24") (pintype "passive"))
      (node (ref "U2") (pin "AE26") (pinfunction "VSS_AE26") (pintype "passive"))
      (node (ref "U2") (pin "AE28") (pinfunction "VSS_AE28") (pintype "passive"))
      (node (ref "U2") (pin "AE30") (pinfunction "VSS_AE30") (pintype "passive"))
      (node (ref "U2") (pin "AE32") (pinfunction "VSS_AE32") (pintype "passive"))
      (node (ref "U2") (pin "AE5") (pinfunction "VSS_AE5") (pintype "passive"))
      (node (ref "U2") (pin "AE7") (pinfunction "VSS_AE7") (pintype "passive"))
      (node (ref "U2") (pin "AE9") (pinfunction "VSS_AE9") (pintype "passive"))
      (node (ref "U2") (pin "AF10") (pinfunction "VSS_AF10") (pintype "passive"))
      (node (ref "U2") (pin "AF12") (pinfunction "VSS_AF12") (pintype "passive"))
      (node (ref "U2") (pin "AF14") (pinfunction "VSS_AF14") (pintype "passive"))
      (node (ref "U2") (pin "AF16") (pinfunction "VSS_AF16") (pintype "passive"))
      (node (ref "U2") (pin "AF18") (pinfunction "VSS_AF18") (pintype "passive"))
      (node (ref "U2") (pin "AF19") (pinfunction "VSS_AF19") (pintype "passive"))
      (node (ref "U2") (pin "AF21") (pinfunction "VSS_AF21") (pintype "passive"))
      (node (ref "U2") (pin "AF23") (pinfunction "VSS_AF23") (pintype "passive"))
      (node (ref "U2") (pin "AF25") (pinfunction "VSS_AF25") (pintype "passive"))
      (node (ref "U2") (pin "AF27") (pinfunction "VSS_AF27") (pintype "passive"))
      (node (ref "U2") (pin "AF29") (pinfunction "VSS_AF29") (pintype "passive"))
      (node (ref "U2") (pin "AF31") (pinfunction "VSS_AF31") (pintype "passive"))
      (node (ref "U2") (pin "AF35") (pinfunction "VSS_AF35") (pintype "passive"))
      (node (ref "U2") (pin "AF8") (pinfunction "VSS_AF8") (pintype "passive"))
      (node (ref "U2") (pin "AG1") (pinfunction "VSS_AG1") (pintype "passive"))
      (node (ref "U2") (pin "AG11") (pinfunction "VSS_AG11") (pintype "passive"))
      (node (ref "U2") (pin "AG13") (pinfunction "VSS_AG13") (pintype "passive"))
      (node (ref "U2") (pin "AG15") (pinfunction "VSS_AG15") (pintype "passive"))
      (node (ref "U2") (pin "AG17") (pinfunction "VSS_AG17") (pintype "passive"))
      (node (ref "U2") (pin "AG20") (pinfunction "VSS_AG20") (pintype "passive"))
      (node (ref "U2") (pin "AG22") (pinfunction "VSS_AG22") (pintype "passive"))
      (node (ref "U2") (pin "AG24") (pinfunction "VSS_AG24") (pintype "passive"))
      (node (ref "U2") (pin "AG26") (pinfunction "VSS_AG26") (pintype "passive"))
      (node (ref "U2") (pin "AG28") (pinfunction "VSS_AG28") (pintype "passive"))
      (node (ref "U2") (pin "AG30") (pinfunction "VSS_AG30") (pintype "passive"))
      (node (ref "U2") (pin "AG32") (pinfunction "VSS_AG32") (pintype "passive"))
      (node (ref "U2") (pin "AG5") (pinfunction "VSS_AG5") (pintype "passive"))
      (node (ref "U2") (pin "AG7") (pinfunction "VSS_AG7") (pintype "passive"))
      (node (ref "U2") (pin "AG9") (pinfunction "VSS_AG9") (pintype "passive"))
      (node (ref "U2") (pin "AH10") (pinfunction "VSS_AH10") (pintype "passive"))
      (node (ref "U2") (pin "AH12") (pinfunction "VSS_AH12") (pintype "passive"))
      (node (ref "U2") (pin "AH14") (pinfunction "VSS_AH14") (pintype "passive"))
      (node (ref "U2") (pin "AH16") (pinfunction "VSS_AH16") (pintype "passive"))
      (node (ref "U2") (pin "AH18") (pinfunction "VSS_AH18") (pintype "passive"))
      (node (ref "U2") (pin "AH19") (pinfunction "VSS_AH19") (pintype "passive"))
      (node (ref "U2") (pin "AH2") (pinfunction "VSS_AH2") (pintype "passive"))
      (node (ref "U2") (pin "AH21") (pinfunction "VSS_AH21") (pintype "passive"))
      (node (ref "U2") (pin "AH23") (pinfunction "VSS_AH23") (pintype "passive"))
      (node (ref "U2") (pin "AH25") (pinfunction "VSS_AH25") (pintype "passive"))
      (node (ref "U2") (pin "AH27") (pinfunction "VSS_AH27") (pintype "passive"))
      (node (ref "U2") (pin "AH29") (pinfunction "VSS_AH29") (pintype "passive"))
      (node (ref "U2") (pin "AH31") (pinfunction "VSS_AH31") (pintype "passive"))
      (node (ref "U2") (pin "AH6") (pinfunction "VSS_AH6") (pintype "passive"))
      (node (ref "U2") (pin "AH8") (pinfunction "VSS_AH8") (pintype "passive"))
      (node (ref "U2") (pin "AJ11") (pinfunction "VSS_AJ11") (pintype "passive"))
      (node (ref "U2") (pin "AJ13") (pinfunction "VSS_AJ13") (pintype "passive"))
      (node (ref "U2") (pin "AJ15") (pinfunction "VSS_AJ15") (pintype "passive"))
      (node (ref "U2") (pin "AJ17") (pinfunction "VSS_AJ17") (pintype "passive"))
      (node (ref "U2") (pin "AJ20") (pinfunction "VSS_AJ20") (pintype "passive"))
      (node (ref "U2") (pin "AJ22") (pinfunction "VSS_AJ22") (pintype "passive"))
      (node (ref "U2") (pin "AJ24") (pinfunction "VSS_AJ24") (pintype "passive"))
      (node (ref "U2") (pin "AJ26") (pinfunction "VSS_AJ26") (pintype "passive"))
      (node (ref "U2") (pin "AJ28") (pinfunction "VSS_AJ28") (pintype "passive"))
      (node (ref "U2") (pin "AJ30") (pinfunction "VSS_AJ30") (pintype "passive"))
      (node (ref "U2") (pin "AJ32") (pinfunction "VSS_AJ32") (pintype "passive"))
      (node (ref "U2") (pin "AJ36") (pinfunction "VSS_AJ36") (pintype "passive"))
      (node (ref "U2") (pin "AJ5") (pinfunction "VSS_AJ5") (pintype "passive"))
      (node (ref "U2") (pin "AJ7") (pinfunction "VSS_AJ7") (pintype "passive"))
      (node (ref "U2") (pin "AJ9") (pinfunction "VSS_AJ9") (pintype "passive"))
      (node (ref "U2") (pin "AK10") (pinfunction "VSS_AK10") (pintype "passive"))
      (node (ref "U2") (pin "AK12") (pinfunction "VSS_AK12") (pintype "passive"))
      (node (ref "U2") (pin "AK14") (pinfunction "VSS_AK14") (pintype "passive"))
      (node (ref "U2") (pin "AK16") (pinfunction "VSS_AK16") (pintype "passive"))
      (node (ref "U2") (pin "AK18") (pinfunction "VSS_AK18") (pintype "passive"))
      (node (ref "U2") (pin "AK19") (pinfunction "VSS_AK19") (pintype "passive"))
      (node (ref "U2") (pin "AK21") (pinfunction "VSS_AK21") (pintype "passive"))
      (node (ref "U2") (pin "AK23") (pinfunction "VSS_AK23") (pintype "passive"))
      (node (ref "U2") (pin "AK25") (pinfunction "VSS_AK25") (pintype "passive"))
      (node (ref "U2") (pin "AK27") (pinfunction "VSS_AK27") (pintype "passive"))
      (node (ref "U2") (pin "AK29") (pinfunction "VSS_AK29") (pintype "passive"))
      (node (ref "U2") (pin "AK31") (pinfunction "VSS_AK31") (pintype "passive"))
      (node (ref "U2") (pin "AK33") (pinfunction "VSS_AK33") (pintype "passive"))
      (node (ref "U2") (pin "AK6") (pinfunction "VSS_AK6") (pintype "passive"))
      (node (ref "U2") (pin "AK8") (pinfunction "VSS_AK8") (pintype "passive"))
      (node (ref "U2") (pin "AL11") (pinfunction "VSS_AL11") (pintype "passive"))
      (node (ref "U2") (pin "AL13") (pinfunction "VSS_AL13") (pintype "passive"))
      (node (ref "U2") (pin "AL15") (pinfunction "VSS_AL15") (pintype "passive"))
      (node (ref "U2") (pin "AL17") (pinfunction "VSS_AL17") (pintype "passive"))
      (node (ref "U2") (pin "AL20") (pinfunction "VSS_AL20") (pintype "passive"))
      (node (ref "U2") (pin "AL22") (pinfunction "VSS_AL22") (pintype "passive"))
      (node (ref "U2") (pin "AL24") (pinfunction "VSS_AL24") (pintype "passive"))
      (node (ref "U2") (pin "AL28") (pinfunction "VSS_AL28") (pintype "passive"))
      (node (ref "U2") (pin "AL3") (pinfunction "VSS_AL3") (pintype "passive"))
      (node (ref "U2") (pin "AL30") (pinfunction "VSS_AL30") (pintype "passive"))
      (node (ref "U2") (pin "AL5") (pinfunction "VSS_AL5") (pintype "passive"))
      (node (ref "U2") (pin "AL7") (pinfunction "VSS_AL7") (pintype "passive"))
      (node (ref "U2") (pin "AL9") (pinfunction "VSS_AL9") (pintype "passive"))
      (node (ref "U2") (pin "AM10") (pinfunction "VSS_AM10") (pintype "passive"))
      (node (ref "U2") (pin "AM12") (pinfunction "VSS_AM12") (pintype "passive"))
      (node (ref "U2") (pin "AM14") (pinfunction "VSS_AM14") (pintype "passive"))
      (node (ref "U2") (pin "AM16") (pinfunction "VSS_AM16") (pintype "passive"))
      (node (ref "U2") (pin "AM18") (pinfunction "VSS_AM18") (pintype "passive"))
      (node (ref "U2") (pin "AM20") (pinfunction "VSS_AM20") (pintype "passive"))
      (node (ref "U2") (pin "AM21") (pinfunction "VSS_AM21") (pintype "passive"))
      (node (ref "U2") (pin "AM23") (pinfunction "VSS_AM23") (pintype "passive"))
      (node (ref "U2") (pin "AM25") (pinfunction "VSS_AM25") (pintype "passive"))
      (node (ref "U2") (pin "AM27") (pinfunction "VSS_AM27") (pintype "passive"))
      (node (ref "U2") (pin "AM29") (pinfunction "VSS_AM29") (pintype "passive"))
      (node (ref "U2") (pin "AM31") (pinfunction "VSS_AM31") (pintype "passive"))
      (node (ref "U2") (pin "AM35") (pinfunction "VSS_AM35") (pintype "passive"))
      (node (ref "U2") (pin "AM8") (pinfunction "VSS_AM8") (pintype "passive"))
      (node (ref "U2") (pin "AN17") (pinfunction "VSS_AN17") (pintype "passive"))
      (node (ref "U2") (pin "AN24") (pinfunction "VSS_AN24") (pintype "passive"))
      (node (ref "U2") (pin "AN34") (pinfunction "VSS_AN34") (pintype "passive"))
      (node (ref "U2") (pin "AN7") (pinfunction "VSS_AN7") (pintype "passive"))
      (node (ref "U2") (pin "AP14") (pinfunction "VSS_AP14") (pintype "passive"))
      (node (ref "U2") (pin "AP18") (pinfunction "VSS_AP18") (pintype "passive"))
      (node (ref "U2") (pin "AP21") (pinfunction "VSS_AP21") (pintype "passive"))
      (node (ref "U2") (pin "AP31") (pinfunction "VSS_AP31") (pintype "passive"))
      (node (ref "U2") (pin "AP4") (pinfunction "VSS_AP4") (pintype "passive"))
      (node (ref "U2") (pin "AR1") (pinfunction "VSS_AR1") (pintype "passive"))
      (node (ref "U2") (pin "AR11") (pinfunction "VSS_AR11") (pintype "passive"))
      (node (ref "U2") (pin "AR28") (pinfunction "VSS_AR28") (pintype "passive"))
      (node (ref "U2") (pin "AR36") (pinfunction "VSS_AR36") (pintype "passive"))
      (node (ref "U2") (pin "AR5") (pinfunction "VSS_AR5") (pintype "passive"))
      (node (ref "U2") (pin "AT1") (pinfunction "VSS_AT1") (pintype "passive"))
      (node (ref "U2") (pin "AT18") (pinfunction "VSS_AT18") (pintype "passive"))
      (node (ref "U2") (pin "AT2") (pinfunction "VSS_AT2") (pintype "passive"))
      (node (ref "U2") (pin "AT25") (pinfunction "VSS_AT25") (pintype "passive"))
      (node (ref "U2") (pin "AT27") (pinfunction "VSS_AT27") (pintype "passive"))
      (node (ref "U2") (pin "AT35") (pinfunction "VSS_AT35") (pintype "passive"))
      (node (ref "U2") (pin "AT36") (pinfunction "VSS_AT36") (pintype "passive"))
      (node (ref "U2") (pin "AT8") (pinfunction "VSS_AT8") (pintype "passive"))
      (node (ref "U2") (pin "B1") (pinfunction "VSS_B1") (pintype "passive"))
      (node (ref "U2") (pin "B26") (pinfunction "VSS_B26") (pintype "passive"))
      (node (ref "U2") (pin "B32") (pinfunction "VSS_B32") (pintype "passive"))
      (node (ref "U2") (pin "B36") (pinfunction "VSS_B36") (pintype "passive"))
      (node (ref "U2") (pin "B9") (pinfunction "VSS_B9") (pintype "passive"))
      (node (ref "U2") (pin "C16") (pinfunction "VSS_C16") (pintype "passive"))
      (node (ref "U2") (pin "C19") (pinfunction "VSS_C19") (pintype "passive"))
      (node (ref "U2") (pin "C23") (pinfunction "VSS_C23") (pintype "passive"))
      (node (ref "U2") (pin "C33") (pinfunction "VSS_C33") (pintype "passive"))
      (node (ref "U2") (pin "C6") (pinfunction "VSS_C6") (pintype "passive"))
      (node (ref "U2") (pin "D13") (pinfunction "VSS_D13") (pintype "passive"))
      (node (ref "U2") (pin "D20") (pinfunction "VSS_D20") (pintype "passive"))
      (node (ref "U2") (pin "D3") (pinfunction "VSS_D3") (pintype "passive"))
      (node (ref "U2") (pin "D30") (pinfunction "VSS_D30") (pintype "passive"))
      (node (ref "U2") (pin "E10") (pinfunction "VSS_E10") (pintype "passive"))
      (node (ref "U2") (pin "E12") (pinfunction "VSS_E12") (pintype "passive"))
      (node (ref "U2") (pin "E14") (pinfunction "VSS_E14") (pintype "passive"))
      (node (ref "U2") (pin "E16") (pinfunction "VSS_E16") (pintype "passive"))
      (node (ref "U2") (pin "E17") (pinfunction "VSS_E17") (pintype "passive"))
      (node (ref "U2") (pin "E19") (pinfunction "VSS_E19") (pintype "passive"))
      (node (ref "U2") (pin "E2") (pinfunction "VSS_E2") (pintype "passive"))
      (node (ref "U2") (pin "E21") (pinfunction "VSS_E21") (pintype "passive"))
      (node (ref "U2") (pin "E23") (pinfunction "VSS_E23") (pintype "passive"))
      (node (ref "U2") (pin "E25") (pinfunction "VSS_E25") (pintype "passive"))
      (node (ref "U2") (pin "E27") (pinfunction "VSS_E27") (pintype "passive"))
      (node (ref "U2") (pin "E29") (pinfunction "VSS_E29") (pintype "passive"))
      (node (ref "U2") (pin "E6") (pinfunction "VSS_E6") (pintype "passive"))
      (node (ref "U2") (pin "E8") (pinfunction "VSS_E8") (pintype "passive"))
      (node (ref "U2") (pin "F13") (pinfunction "VSS_F13") (pintype "passive"))
      (node (ref "U2") (pin "F15") (pinfunction "VSS_F15") (pintype "passive"))
      (node (ref "U2") (pin "F17") (pinfunction "VSS_F17") (pintype "passive"))
      (node (ref "U2") (pin "F20") (pinfunction "VSS_F20") (pintype "passive"))
      (node (ref "U2") (pin "F22") (pinfunction "VSS_F22") (pintype "passive"))
      (node (ref "U2") (pin "F24") (pinfunction "VSS_F24") (pintype "passive"))
      (node (ref "U2") (pin "F26") (pinfunction "VSS_F26") (pintype "passive"))
      (node (ref "U2") (pin "F28") (pinfunction "VSS_F28") (pintype "passive"))
      (node (ref "U2") (pin "F30") (pinfunction "VSS_F30") (pintype "passive"))
      (node (ref "U2") (pin "F32") (pinfunction "VSS_F32") (pintype "passive"))
      (node (ref "U2") (pin "F34") (pinfunction "VSS_F34") (pintype "passive"))
      (node (ref "U2") (pin "F7") (pinfunction "VSS_F7") (pintype "passive"))
      (node (ref "U2") (pin "F9") (pinfunction "VSS_F9") (pintype "passive"))
      (node (ref "U2") (pin "G10") (pinfunction "VSS_G10") (pintype "passive"))
      (node (ref "U2") (pin "G12") (pinfunction "VSS_G12") (pintype "passive"))
      (node (ref "U2") (pin "G14") (pinfunction "VSS_G14") (pintype "passive"))
      (node (ref "U2") (pin "G16") (pinfunction "VSS_G16") (pintype "passive"))
      (node (ref "U2") (pin "G18") (pinfunction "VSS_G18") (pintype "passive"))
      (node (ref "U2") (pin "G19") (pinfunction "VSS_G19") (pintype "passive"))
      (node (ref "U2") (pin "G21") (pinfunction "VSS_G21") (pintype "passive"))
      (node (ref "U2") (pin "G23") (pinfunction "VSS_G23") (pintype "passive"))
      (node (ref "U2") (pin "G25") (pinfunction "VSS_G25") (pintype "passive"))
      (node (ref "U2") (pin "G27") (pinfunction "VSS_G27") (pintype "passive"))
      (node (ref "U2") (pin "G29") (pinfunction "VSS_G29") (pintype "passive"))
      (node (ref "U2") (pin "G31") (pinfunction "VSS_G31") (pintype "passive"))
      (node (ref "U2") (pin "G4") (pinfunction "VSS_G4") (pintype "passive"))
      (node (ref "U2") (pin "G6") (pinfunction "VSS_G6") (pintype "passive"))
      (node (ref "U2") (pin "G8") (pinfunction "VSS_G8") (pintype "passive"))
      (node (ref "U2") (pin "H1") (pinfunction "VSS_H1") (pintype "passive"))
      (node (ref "U2") (pin "H11") (pinfunction "VSS_H11") (pintype "passive"))
      (node (ref "U2") (pin "H13") (pinfunction "VSS_H13") (pintype "passive"))
      (node (ref "U2") (pin "H15") (pinfunction "VSS_H15") (pintype "passive"))
      (node (ref "U2") (pin "H17") (pinfunction "VSS_H17") (pintype "passive"))
      (node (ref "U2") (pin "H20") (pinfunction "VSS_H20") (pintype "passive"))
      (node (ref "U2") (pin "H22") (pinfunction "VSS_H22") (pintype "passive"))
      (node (ref "U2") (pin "H24") (pinfunction "VSS_H24") (pintype "passive"))
      (node (ref "U2") (pin "H26") (pinfunction "VSS_H26") (pintype "passive"))
      (node (ref "U2") (pin "H28") (pinfunction "VSS_H28") (pintype "passive"))
      (node (ref "U2") (pin "H30") (pinfunction "VSS_H30") (pintype "passive"))
      (node (ref "U2") (pin "H32") (pinfunction "VSS_H32") (pintype "passive"))
      (node (ref "U2") (pin "H5") (pinfunction "VSS_H5") (pintype "passive"))
      (node (ref "U2") (pin "H7") (pinfunction "VSS_H7") (pintype "passive"))
      (node (ref "U2") (pin "H9") (pinfunction "VSS_H9") (pintype "passive"))
      (node (ref "U2") (pin "J10") (pinfunction "VSS_J10") (pintype "passive"))
      (node (ref "U2") (pin "J12") (pinfunction "VSS_J12") (pintype "passive"))
      (node (ref "U2") (pin "J14") (pinfunction "VSS_J14") (pintype "passive"))
      (node (ref "U2") (pin "J16") (pinfunction "VSS_J16") (pintype "passive"))
      (node (ref "U2") (pin "J18") (pinfunction "VSS_J18") (pintype "passive"))
      (node (ref "U2") (pin "J19") (pinfunction "VSS_J19") (pintype "passive"))
      (node (ref "U2") (pin "J21") (pinfunction "VSS_J21") (pintype "passive"))
      (node (ref "U2") (pin "J23") (pinfunction "VSS_J23") (pintype "passive"))
      (node (ref "U2") (pin "J25") (pinfunction "VSS_J25") (pintype "passive"))
      (node (ref "U2") (pin "J27") (pinfunction "VSS_J27") (pintype "passive"))
      (node (ref "U2") (pin "J29") (pinfunction "VSS_J29") (pintype "passive"))
      (node (ref "U2") (pin "J31") (pinfunction "VSS_J31") (pintype "passive"))
      (node (ref "U2") (pin "J35") (pinfunction "VSS_J35") (pintype "passive"))
      (node (ref "U2") (pin "J6") (pinfunction "VSS_J6") (pintype "passive"))
      (node (ref "U2") (pin "J8") (pinfunction "VSS_J8") (pintype "passive"))
      (node (ref "U2") (pin "K11") (pinfunction "VSS_K11") (pintype "passive"))
      (node (ref "U2") (pin "K13") (pinfunction "VSS_K13") (pintype "passive"))
      (node (ref "U2") (pin "K15") (pinfunction "VSS_K15") (pintype "passive"))
      (node (ref "U2") (pin "K17") (pinfunction "VSS_K17") (pintype "passive"))
      (node (ref "U2") (pin "K20") (pinfunction "VSS_K20") (pintype "passive"))
      (node (ref "U2") (pin "K22") (pinfunction "VSS_K22") (pintype "passive"))
      (node (ref "U2") (pin "K24") (pinfunction "VSS_K24") (pintype "passive"))
      (node (ref "U2") (pin "K26") (pinfunction "VSS_K26") (pintype "passive"))
      (node (ref "U2") (pin "K28") (pinfunction "VSS_K28") (pintype "passive"))
      (node (ref "U2") (pin "K30") (pinfunction "VSS_K30") (pintype "passive"))
      (node (ref "U2") (pin "K32") (pinfunction "VSS_K32") (pintype "passive"))
      (node (ref "U2") (pin "K36") (pinfunction "VSS_K36") (pintype "passive"))
      (node (ref "U2") (pin "K5") (pinfunction "VSS_K5") (pintype "passive"))
      (node (ref "U2") (pin "K7") (pinfunction "VSS_K7") (pintype "passive"))
      (node (ref "U2") (pin "K9") (pinfunction "VSS_K9") (pintype "passive"))
      (node (ref "U2") (pin "L10") (pinfunction "VSS_L10") (pintype "passive"))
      (node (ref "U2") (pin "L12") (pinfunction "VSS_L12") (pintype "passive"))
      (node (ref "U2") (pin "L14") (pinfunction "VSS_L14") (pintype "passive"))
      (node (ref "U2") (pin "L16") (pinfunction "VSS_L16") (pintype "passive"))
      (node (ref "U2") (pin "L18") (pinfunction "VSS_L18") (pintype "passive"))
      (node (ref "U2") (pin "L19") (pinfunction "VSS_L19") (pintype "passive"))
      (node (ref "U2") (pin "L2") (pinfunction "VSS_L2") (pintype "passive"))
      (node (ref "U2") (pin "L21") (pinfunction "VSS_L21") (pintype "passive"))
      (node (ref "U2") (pin "L23") (pinfunction "VSS_L23") (pintype "passive"))
      (node (ref "U2") (pin "L25") (pinfunction "VSS_L25") (pintype "passive"))
      (node (ref "U2") (pin "L27") (pinfunction "VSS_L27") (pintype "passive"))
      (node (ref "U2") (pin "L29") (pinfunction "VSS_L29") (pintype "passive"))
      (node (ref "U2") (pin "L6") (pinfunction "VSS_L6") (pintype "passive"))
      (node (ref "U2") (pin "L8") (pinfunction "VSS_L8") (pintype "passive"))
      (node (ref "U2") (pin "M11") (pinfunction "VSS_M11") (pintype "passive"))
      (node (ref "U2") (pin "M13") (pinfunction "VSS_M13") (pintype "passive"))
      (node (ref "U2") (pin "M15") (pinfunction "VSS_M15") (pintype "passive"))
      (node (ref "U2") (pin "M17") (pinfunction "VSS_M17") (pintype "passive"))
      (node (ref "U2") (pin "M20") (pinfunction "VSS_M20") (pintype "passive"))
      (node (ref "U2") (pin "M22") (pinfunction "VSS_M22") (pintype "passive"))
      (node (ref "U2") (pin "M24") (pinfunction "VSS_M24") (pintype "passive"))
      (node (ref "U2") (pin "M26") (pinfunction "VSS_M26") (pintype "passive"))
      (node (ref "U2") (pin "M28") (pinfunction "VSS_M28") (pintype "passive"))
      (node (ref "U2") (pin "M30") (pinfunction "VSS_M30") (pintype "passive"))
      (node (ref "U2") (pin "M32") (pinfunction "VSS_M32") (pintype "passive"))
      (node (ref "U2") (pin "M36") (pinfunction "VSS_M36") (pintype "passive"))
      (node (ref "U2") (pin "M5") (pinfunction "VSS_M5") (pintype "passive"))
      (node (ref "U2") (pin "M7") (pinfunction "VSS_M7") (pintype "passive"))
      (node (ref "U2") (pin "M9") (pinfunction "VSS_M9") (pintype "passive"))
      (node (ref "U2") (pin "N10") (pinfunction "VSS_N10") (pintype "passive"))
      (node (ref "U2") (pin "N12") (pinfunction "VSS_N12") (pintype "passive"))
      (node (ref "U2") (pin "N14") (pinfunction "VSS_N14") (pintype "passive"))
      (node (ref "U2") (pin "N16") (pinfunction "VSS_N16") (pintype "passive"))
      (node (ref "U2") (pin "N18") (pinfunction "VSS_N18") (pintype "passive"))
      (node (ref "U2") (pin "N19") (pinfunction "VSS_N19") (pintype "passive"))
      (node (ref "U2") (pin "N21") (pinfunction "VSS_N21") (pintype "passive"))
      (node (ref "U2") (pin "N23") (pinfunction "VSS_N23") (pintype "passive"))
      (node (ref "U2") (pin "N25") (pinfunction "VSS_N25") (pintype "passive"))
      (node (ref "U2") (pin "N27") (pinfunction "VSS_N27") (pintype "passive"))
      (node (ref "U2") (pin "N29") (pinfunction "VSS_N29") (pintype "passive"))
      (node (ref "U2") (pin "N31") (pinfunction "VSS_N31") (pintype "passive"))
      (node (ref "U2") (pin "N33") (pinfunction "VSS_N33") (pintype "passive"))
      (node (ref "U2") (pin "N6") (pinfunction "VSS_N6") (pintype "passive"))
      (node (ref "U2") (pin "N8") (pinfunction "VSS_N8") (pintype "passive"))
      (node (ref "U2") (pin "P11") (pinfunction "VSS_P11") (pintype "passive"))
      (node (ref "U2") (pin "P13") (pinfunction "VSS_P13") (pintype "passive"))
      (node (ref "U2") (pin "P15") (pinfunction "VSS_P15") (pintype "passive"))
      (node (ref "U2") (pin "P17") (pinfunction "VSS_P17") (pintype "passive"))
      (node (ref "U2") (pin "P20") (pinfunction "VSS_P20") (pintype "passive"))
      (node (ref "U2") (pin "P22") (pinfunction "VSS_P22") (pintype "passive"))
      (node (ref "U2") (pin "P24") (pinfunction "VSS_P24") (pintype "passive"))
      (node (ref "U2") (pin "P26") (pinfunction "VSS_P26") (pintype "passive"))
      (node (ref "U2") (pin "P28") (pinfunction "VSS_P28") (pintype "passive"))
      (node (ref "U2") (pin "P3") (pinfunction "VSS_P3") (pintype "passive"))
      (node (ref "U2") (pin "P30") (pinfunction "VSS_P30") (pintype "passive"))
      (node (ref "U2") (pin "P32") (pinfunction "VSS_P32") (pintype "passive"))
      (node (ref "U2") (pin "P5") (pinfunction "VSS_P5") (pintype "passive"))
      (node (ref "U2") (pin "P7") (pinfunction "VSS_P7") (pintype "passive"))
      (node (ref "U2") (pin "P9") (pinfunction "VSS_P9") (pintype "passive"))
      (node (ref "U2") (pin "R10") (pinfunction "VSS_R10") (pintype "passive"))
      (node (ref "U2") (pin "R12") (pinfunction "VSS_R12") (pintype "passive"))
      (node (ref "U2") (pin "R14") (pinfunction "VSS_R14") (pintype "passive"))
      (node (ref "U2") (pin "R16") (pinfunction "VSS_R16") (pintype "passive"))
      (node (ref "U2") (pin "R18") (pinfunction "VSS_R18") (pintype "passive"))
      (node (ref "U2") (pin "R19") (pinfunction "VSS_R19") (pintype "passive"))
      (node (ref "U2") (pin "R21") (pinfunction "VSS_R21") (pintype "passive"))
      (node (ref "U2") (pin "R23") (pinfunction "VSS_R23") (pintype "passive"))
      (node (ref "U2") (pin "R25") (pinfunction "VSS_R25") (pintype "passive"))
      (node (ref "U2") (pin "R27") (pinfunction "VSS_R27") (pintype "passive"))
      (node (ref "U2") (pin "R29") (pinfunction "VSS_R29") (pintype "passive"))
      (node (ref "U2") (pin "R31") (pinfunction "VSS_R31") (pintype "passive"))
      (node (ref "U2") (pin "R6") (pinfunction "VSS_R6") (pintype "passive"))
      (node (ref "U2") (pin "R8") (pinfunction "VSS_R8") (pintype "passive"))
      (node (ref "U2") (pin "T11") (pinfunction "VSS_T11") (pintype "passive"))
      (node (ref "U2") (pin "T13") (pinfunction "VSS_T13") (pintype "passive"))
      (node (ref "U2") (pin "T15") (pinfunction "VSS_T15") (pintype "passive"))
      (node (ref "U2") (pin "T17") (pinfunction "VSS_T17") (pintype "passive"))
      (node (ref "U2") (pin "T20") (pinfunction "VSS_T20") (pintype "passive"))
      (node (ref "U2") (pin "T22") (pinfunction "VSS_T22") (pintype "passive"))
      (node (ref "U2") (pin "T24") (pinfunction "VSS_T24") (pintype "passive"))
      (node (ref "U2") (pin "T26") (pinfunction "VSS_T26") (pintype "passive"))
      (node (ref "U2") (pin "T28") (pinfunction "VSS_T28") (pintype "passive"))
      (node (ref "U2") (pin "T30") (pinfunction "VSS_T30") (pintype "passive"))
      (node (ref "U2") (pin "T32") (pinfunction "VSS_T32") (pintype "passive"))
      (node (ref "U2") (pin "T34") (pinfunction "VSS_T34") (pintype "passive"))
      (node (ref "U2") (pin "T5") (pinfunction "VSS_T5") (pintype "passive"))
      (node (ref "U2") (pin "T7") (pinfunction "VSS_T7") (pintype "passive"))
      (node (ref "U2") (pin "T9") (pinfunction "VSS_T9") (pintype "passive"))
      (node (ref "U2") (pin "U10") (pinfunction "VSS_U10") (pintype "passive"))
      (node (ref "U2") (pin "U12") (pinfunction "VSS_U12") (pintype "passive"))
      (node (ref "U2") (pin "U14") (pinfunction "VSS_U14") (pintype "passive"))
      (node (ref "U2") (pin "U16") (pinfunction "VSS_U16") (pintype "passive"))
      (node (ref "U2") (pin "U18") (pinfunction "VSS_U18") (pintype "passive"))
      (node (ref "U2") (pin "U19") (pinfunction "VSS_U19") (pintype "passive"))
      (node (ref "U2") (pin "U21") (pinfunction "VSS_U21") (pintype "passive"))
      (node (ref "U2") (pin "U23") (pinfunction "VSS_U23") (pintype "passive"))
      (node (ref "U2") (pin "U25") (pinfunction "VSS_U25") (pintype "passive"))
      (node (ref "U2") (pin "U27") (pinfunction "VSS_U27") (pintype "passive"))
      (node (ref "U2") (pin "U29") (pinfunction "VSS_U29") (pintype "passive"))
      (node (ref "U2") (pin "U31") (pinfunction "VSS_U31") (pintype "passive"))
      (node (ref "U2") (pin "U32") (pinfunction "VSS_U32") (pintype "passive"))
      (node (ref "U2") (pin "U4") (pinfunction "VSS_U4") (pintype "passive"))
      (node (ref "U2") (pin "U6") (pinfunction "VSS_U6") (pintype "passive"))
      (node (ref "U2") (pin "U8") (pinfunction "VSS_U8") (pintype "passive"))
      (node (ref "U2") (pin "V1") (pinfunction "VSS_V1") (pintype "passive"))
      (node (ref "U2") (pin "V11") (pinfunction "VSS_V11") (pintype "passive"))
      (node (ref "U2") (pin "V13") (pinfunction "VSS_V13") (pintype "passive"))
      (node (ref "U2") (pin "V15") (pinfunction "VSS_V15") (pintype "passive"))
      (node (ref "U2") (pin "V17") (pinfunction "VSS_V17") (pintype "passive"))
      (node (ref "U2") (pin "V20") (pinfunction "VSS_V20") (pintype "passive"))
      (node (ref "U2") (pin "V22") (pinfunction "VSS_V22") (pintype "passive"))
      (node (ref "U2") (pin "V24") (pinfunction "VSS_V24") (pintype "passive"))
      (node (ref "U2") (pin "V26") (pinfunction "VSS_V26") (pintype "passive"))
      (node (ref "U2") (pin "V28") (pinfunction "VSS_V28") (pintype "passive"))
      (node (ref "U2") (pin "V3") (pinfunction "VSS_V3") (pintype "passive"))
      (node (ref "U2") (pin "V30") (pinfunction "VSS_V30") (pintype "passive"))
      (node (ref "U2") (pin "V5") (pinfunction "VSS_V5") (pintype "passive"))
      (node (ref "U2") (pin "V7") (pinfunction "VSS_V7") (pintype "passive"))
      (node (ref "U2") (pin "V9") (pinfunction "VSS_V9") (pintype "passive"))
      (node (ref "U2") (pin "W11") (pinfunction "VSS_W11") (pintype "passive"))
      (node (ref "U2") (pin "W13") (pinfunction "VSS_W13") (pintype "passive"))
      (node (ref "U2") (pin "W15") (pinfunction "VSS_W15") (pintype "passive"))
      (node (ref "U2") (pin "W17") (pinfunction "VSS_W17") (pintype "passive"))
      (node (ref "U2") (pin "W20") (pinfunction "VSS_W20") (pintype "passive"))
      (node (ref "U2") (pin "W22") (pinfunction "VSS_W22") (pintype "passive"))
      (node (ref "U2") (pin "W24") (pinfunction "VSS_W24") (pintype "passive"))
      (node (ref "U2") (pin "W26") (pinfunction "VSS_W26") (pintype "passive"))
      (node (ref "U2") (pin "W28") (pinfunction "VSS_W28") (pintype "passive"))
      (node (ref "U2") (pin "W30") (pinfunction "VSS_W30") (pintype "passive"))
      (node (ref "U2") (pin "W32") (pinfunction "VSS_W32") (pintype "passive"))
      (node (ref "U2") (pin "W34") (pinfunction "VSS_W34") (pintype "passive"))
      (node (ref "U2") (pin "W36") (pinfunction "VSS_W36") (pintype "passive"))
      (node (ref "U2") (pin "W7") (pinfunction "VSS_W7") (pintype "passive"))
      (node (ref "U2") (pin "W9") (pinfunction "VSS_W9") (pintype "passive"))
      (node (ref "U2") (pin "Y10") (pinfunction "VSS_Y10") (pintype "passive"))
      (node (ref "U2") (pin "Y12") (pinfunction "VSS_Y12") (pintype "passive"))
      (node (ref "U2") (pin "Y14") (pinfunction "VSS_Y14") (pintype "passive"))
      (node (ref "U2") (pin "Y16") (pinfunction "VSS_Y16") (pintype "passive"))
      (node (ref "U2") (pin "Y18") (pinfunction "VSS_Y18") (pintype "passive"))
      (node (ref "U2") (pin "Y19") (pinfunction "VSS_Y19") (pintype "passive"))
      (node (ref "U2") (pin "Y21") (pinfunction "VSS_Y21") (pintype "passive"))
      (node (ref "U2") (pin "Y23") (pinfunction "VSS_Y23") (pintype "passive"))
      (node (ref "U2") (pin "Y25") (pinfunction "VSS_Y25") (pintype "passive"))
      (node (ref "U2") (pin "Y27") (pinfunction "VSS_Y27") (pintype "passive"))
      (node (ref "U2") (pin "Y29") (pinfunction "VSS_Y29") (pintype "passive"))
      (node (ref "U2") (pin "Y31") (pinfunction "VSS_Y31") (pintype "passive"))
      (node (ref "U2") (pin "Y33") (pinfunction "VSS_Y33") (pintype "passive"))
      (node (ref "U2") (pin "Y5") (pinfunction "VSS_Y5") (pintype "passive"))
      (node (ref "U2") (pin "Y6") (pinfunction "VSS_Y6") (pintype "passive"))
      (node (ref "U2") (pin "Y8") (pinfunction "VSS_Y8") (pintype "passive"))
    )
  )
)
